# DC30_Cnet_FluxCapacitor.net
KiCad netlist of a schematic drawn in EAGLE
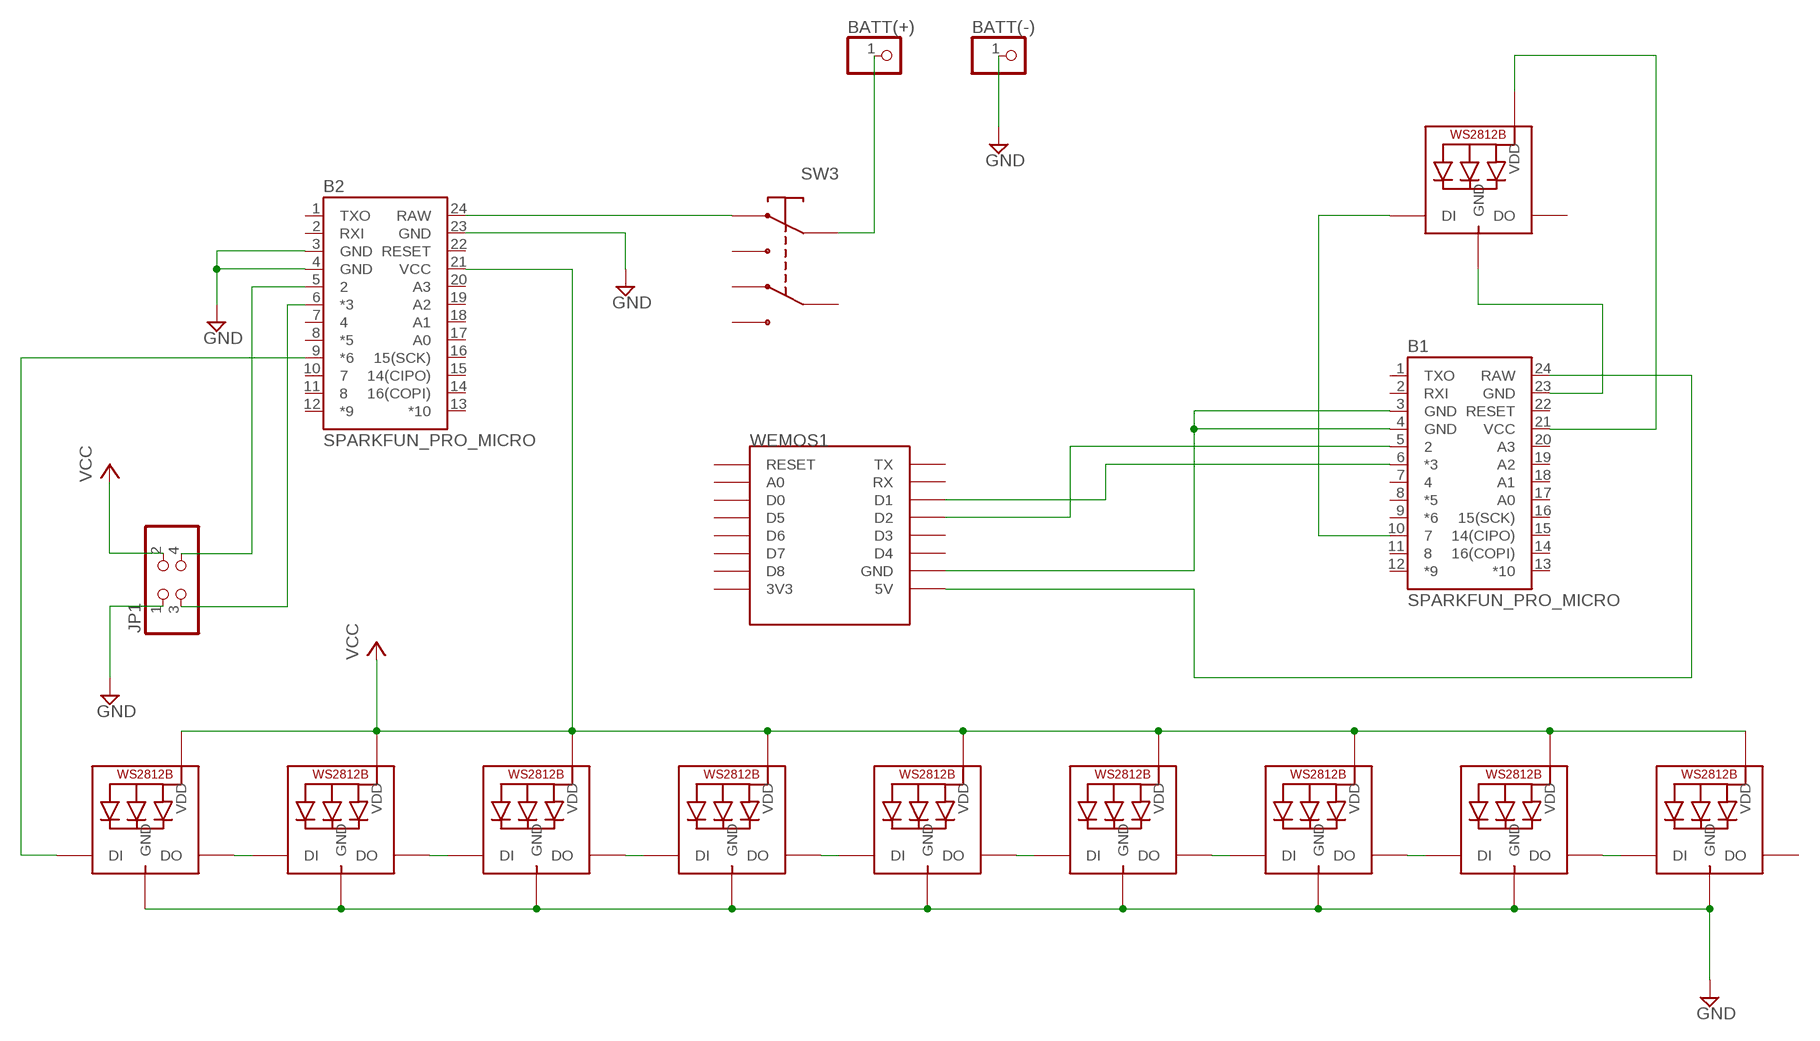
[diagram p0: schematic, sheet 1]

(export (version "E")
  (design (tool "Eeschema 10.0.6"))
  (components
    (comp (ref "B1")
      (value "SPARKFUN_PRO_MICRO")
      (footprint "eagle-import:SPARKFUN_PRO_MICRO")
      (libsource (lib "eagle-import") (part "SPARKFUN_PRO_MICRO"))
    )
    (comp (ref "B2")
      (value "SPARKFUN_PRO_MICRO")
      (footprint "eagle-import:SPARKFUN_PRO_MICRO")
      (libsource (lib "eagle-import") (part "SPARKFUN_PRO_MICRO"))
    )
    (comp (ref "BATT(+)")
      (value "PINHD-1X1")
      (footprint "eagle-import:1X01")
      (libsource (lib "eagle-import") (part "PINHD-1X1"))
    )
    (comp (ref "BATT(-)")
      (value "PINHD-1X1")
      (footprint "eagle-import:1X01")
      (libsource (lib "eagle-import") (part "PINHD-1X1"))
    )
    (comp (ref "JP1")
      (value "PINHD-2X2")
      (footprint "eagle-import:2X02")
      (libsource (lib "eagle-import") (part "PINHD-2X2"))
    )
    (comp (ref "LED1")
      (value "WS2812B5050")
      (footprint "eagle-import:WS2812B")
      (libsource (lib "eagle-import") (part "WS2812B5050"))
    )
    (comp (ref "LED2")
      (value "WS2812B5050")
      (footprint "eagle-import:WS2812B")
      (libsource (lib "eagle-import") (part "WS2812B5050"))
    )
    (comp (ref "LED3")
      (value "WS2812B5050")
      (footprint "eagle-import:WS2812B")
      (libsource (lib "eagle-import") (part "WS2812B5050"))
    )
    (comp (ref "LED4")
      (value "WS2812B5050")
      (footprint "eagle-import:WS2812B")
      (libsource (lib "eagle-import") (part "WS2812B5050"))
    )
    (comp (ref "LED5")
      (value "WS2812B5050")
      (footprint "eagle-import:WS2812B")
      (libsource (lib "eagle-import") (part "WS2812B5050"))
    )
    (comp (ref "LED6")
      (value "WS2812B5050")
      (footprint "eagle-import:WS2812B")
      (libsource (lib "eagle-import") (part "WS2812B5050"))
    )
    (comp (ref "LED7")
      (value "WS2812B5050")
      (footprint "eagle-import:WS2812B")
      (libsource (lib "eagle-import") (part "WS2812B5050"))
    )
    (comp (ref "LED8")
      (value "WS2812B5050")
      (footprint "eagle-import:WS2812B")
      (libsource (lib "eagle-import") (part "WS2812B5050"))
    )
    (comp (ref "LED9")
      (value "WS2812B5050")
      (footprint "eagle-import:WS2812B")
      (libsource (lib "eagle-import") (part "WS2812B5050"))
    )
    (comp (ref "LED10")
      (value "WS2812B5050")
      (footprint "eagle-import:WS2812B")
      (libsource (lib "eagle-import") (part "WS2812B5050"))
    )
    (comp (ref "SW3")
      (value "JS202011AQN")
      (footprint "eagle-import:JS202011AQN")
      (libsource (lib "eagle-import") (part "JS202011AQN"))
    )
    (comp (ref "WEMOS1")
      (value "WEMOS-D1-MINI")
      (footprint "eagle-import:WEMOS-D1-MINI")
      (libsource (lib "eagle-import") (part "WEMOS-D1-MINI"))
    )
  )
  (nets
    (net (code "1") (name "GND") (class "Default")
      (node (ref "B2") (pin "23") (pinfunction "GND_23") (pintype "power_in"))
      (node (ref "B2") (pin "3") (pinfunction "GND_3") (pintype "power_in"))
      (node (ref "B2") (pin "4") (pinfunction "GND_4") (pintype "power_in"))
      (node (ref "BATT(-)") (pin "1") (pinfunction "1_1") (pintype "passive"))
      (node (ref "JP1") (pin "1") (pinfunction "1_1") (pintype "passive"))
      (node (ref "LED1") (pin "3-GND") (pinfunction "GND_3-GND") (pintype "power_in"))
      (node (ref "LED2") (pin "3-GND") (pinfunction "GND_3-GND") (pintype "power_in"))
      (node (ref "LED3") (pin "3-GND") (pinfunction "GND_3-GND") (pintype "power_in"))
      (node (ref "LED4") (pin "3-GND") (pinfunction "GND_3-GND") (pintype "power_in"))
      (node (ref "LED5") (pin "3-GND") (pinfunction "GND_3-GND") (pintype "power_in"))
      (node (ref "LED6") (pin "3-GND") (pinfunction "GND_3-GND") (pintype "power_in"))
      (node (ref "LED7") (pin "3-GND") (pinfunction "GND_3-GND") (pintype "power_in"))
      (node (ref "LED8") (pin "3-GND") (pinfunction "GND_3-GND") (pintype "power_in"))
      (node (ref "LED9") (pin "3-GND") (pinfunction "GND_3-GND") (pintype "power_in"))
    )
    (net (code "2") (name "Net-(B1-*3)") (class "Default")
      (node (ref "B1") (pin "6") (pinfunction "*3_6") (pintype "bidirectional"))
      (node (ref "WEMOS1") (pin "D1") (pinfunction "D1_D1") (pintype "bidirectional"))
    )
    (net (code "3") (name "Net-(B1-2)") (class "Default")
      (node (ref "B1") (pin "5") (pinfunction "2_5") (pintype "bidirectional"))
      (node (ref "WEMOS1") (pin "D2") (pinfunction "D2_D2") (pintype "bidirectional"))
    )
    (net (code "4") (name "Net-(B1-7)") (class "Default")
      (node (ref "B1") (pin "10") (pinfunction "7_10") (pintype "bidirectional"))
      (node (ref "LED10") (pin "4-DIN") (pinfunction "DI_4-DIN") (pintype "input"))
    )
    (net (code "5") (name "Net-(B1-GND-Pad3)") (class "Default")
      (node (ref "B1") (pin "3") (pinfunction "GND_3") (pintype "power_in"))
      (node (ref "B1") (pin "4") (pinfunction "GND_4") (pintype "power_in"))
      (node (ref "WEMOS1") (pin "GND") (pinfunction "GND_GND") (pintype "bidirectional"))
    )
    (net (code "6") (name "Net-(B1-RAW)") (class "Default")
      (node (ref "B1") (pin "24") (pinfunction "RAW_24") (pintype "power_in"))
      (node (ref "WEMOS1") (pin "5V") (pinfunction "5V_5V") (pintype "bidirectional"))
    )
    (net (code "7") (name "Net-(B1-VCC)") (class "Default")
      (node (ref "B1") (pin "21") (pinfunction "VCC_21") (pintype "power_in"))
      (node (ref "LED10") (pin "1-VDD") (pinfunction "VDD_1-VDD") (pintype "power_in"))
    )
    (net (code "8") (name "Net-(B2-*3)") (class "Default")
      (node (ref "B2") (pin "6") (pinfunction "*3_6") (pintype "bidirectional"))
      (node (ref "JP1") (pin "3") (pinfunction "3_3") (pintype "passive"))
    )
    (net (code "9") (name "Net-(B2-*6)") (class "Default")
      (node (ref "B2") (pin "9") (pinfunction "*6_9") (pintype "bidirectional"))
      (node (ref "LED1") (pin "4-DIN") (pinfunction "DI_4-DIN") (pintype "input"))
    )
    (net (code "10") (name "Net-(B2-2)") (class "Default")
      (node (ref "B2") (pin "5") (pinfunction "2_5") (pintype "bidirectional"))
      (node (ref "JP1") (pin "4") (pinfunction "4_4") (pintype "passive"))
    )
    (net (code "11") (name "Net-(B2-RAW)") (class "Default")
      (node (ref "B2") (pin "24") (pinfunction "RAW_24") (pintype "power_in"))
      (node (ref "SW3") (pin "P$1") (pinfunction "1_P$1") (pintype "bidirectional"))
    )
    (net (code "12") (name "Net-(LED1-DO)") (class "Default")
      (node (ref "LED1") (pin "2-DOUT") (pinfunction "DO_2-DOUT") (pintype "output"))
      (node (ref "LED2") (pin "4-DIN") (pinfunction "DI_4-DIN") (pintype "input"))
    )
    (net (code "13") (name "Net-(LED2-DO)") (class "Default")
      (node (ref "LED2") (pin "2-DOUT") (pinfunction "DO_2-DOUT") (pintype "output"))
      (node (ref "LED3") (pin "4-DIN") (pinfunction "DI_4-DIN") (pintype "input"))
    )
    (net (code "14") (name "Net-(LED3-DO)") (class "Default")
      (node (ref "LED3") (pin "2-DOUT") (pinfunction "DO_2-DOUT") (pintype "output"))
      (node (ref "LED4") (pin "4-DIN") (pinfunction "DI_4-DIN") (pintype "input"))
    )
    (net (code "15") (name "Net-(LED4-DO)") (class "Default")
      (node (ref "LED4") (pin "2-DOUT") (pinfunction "DO_2-DOUT") (pintype "output"))
      (node (ref "LED5") (pin "4-DIN") (pinfunction "DI_4-DIN") (pintype "input"))
    )
    (net (code "16") (name "Net-(LED5-DO)") (class "Default")
      (node (ref "LED5") (pin "2-DOUT") (pinfunction "DO_2-DOUT") (pintype "output"))
      (node (ref "LED6") (pin "4-DIN") (pinfunction "DI_4-DIN") (pintype "input"))
    )
    (net (code "17") (name "Net-(LED6-DO)") (class "Default")
      (node (ref "LED6") (pin "2-DOUT") (pinfunction "DO_2-DOUT") (pintype "output"))
      (node (ref "LED7") (pin "4-DIN") (pinfunction "DI_4-DIN") (pintype "input"))
    )
    (net (code "18") (name "Net-(LED7-DO)") (class "Default")
      (node (ref "LED7") (pin "2-DOUT") (pinfunction "DO_2-DOUT") (pintype "output"))
      (node (ref "LED8") (pin "4-DIN") (pinfunction "DI_4-DIN") (pintype "input"))
    )
    (net (code "19") (name "Net-(LED8-DO)") (class "Default")
      (node (ref "LED8") (pin "2-DOUT") (pinfunction "DO_2-DOUT") (pintype "output"))
      (node (ref "LED9") (pin "4-DIN") (pinfunction "DI_4-DIN") (pintype "input"))
    )
    (net (code "20") (name "Net-(LED10-GND)") (class "Default")
      (node (ref "B1") (pin "23") (pinfunction "GND_23") (pintype "power_in"))
      (node (ref "LED10") (pin "3-GND") (pinfunction "GND_3-GND") (pintype "power_in"))
    )
    (net (code "21") (name "Net-(SW3-2)") (class "Default")
      (node (ref "BATT(+)") (pin "1") (pinfunction "1_1") (pintype "passive"))
      (node (ref "SW3") (pin "P$2") (pinfunction "2_P$2") (pintype "bidirectional"))
    )
    (net (code "22") (name "VCC") (class "Default")
      (node (ref "B2") (pin "21") (pinfunction "VCC_21") (pintype "power_in"))
      (node (ref "JP1") (pin "2") (pinfunction "2_2") (pintype "passive"))
      (node (ref "LED1") (pin "1-VDD") (pinfunction "VDD_1-VDD") (pintype "power_in"))
      (node (ref "LED2") (pin "1-VDD") (pinfunction "VDD_1-VDD") (pintype "power_in"))
      (node (ref "LED3") (pin "1-VDD") (pinfunction "VDD_1-VDD") (pintype "power_in"))
      (node (ref "LED4") (pin "1-VDD") (pinfunction "VDD_1-VDD") (pintype "power_in"))
      (node (ref "LED5") (pin "1-VDD") (pinfunction "VDD_1-VDD") (pintype "power_in"))
      (node (ref "LED6") (pin "1-VDD") (pinfunction "VDD_1-VDD") (pintype "power_in"))
      (node (ref "LED7") (pin "1-VDD") (pinfunction "VDD_1-VDD") (pintype "power_in"))
      (node (ref "LED8") (pin "1-VDD") (pinfunction "VDD_1-VDD") (pintype "power_in"))
      (node (ref "LED9") (pin "1-VDD") (pinfunction "VDD_1-VDD") (pintype "power_in"))
    )
    (net (code "23") (name "unconnected-(B1-*5-Pad8)") (class "Default")
      (node (ref "B1") (pin "8") (pinfunction "*5_8") (pintype "bidirectional"))
    )
    (net (code "24") (name "unconnected-(B1-*6-Pad9)") (class "Default")
      (node (ref "B1") (pin "9") (pinfunction "*6_9") (pintype "bidirectional"))
    )
    (net (code "25") (name "unconnected-(B1-*9-Pad12)") (class "Default")
      (node (ref "B1") (pin "12") (pinfunction "*9_12") (pintype "bidirectional"))
    )
    (net (code "26") (name "unconnected-(B1-*10-Pad13)") (class "Default")
      (node (ref "B1") (pin "13") (pinfunction "*10_13") (pintype "bidirectional"))
    )
    (net (code "27") (name "unconnected-(B1-4-Pad7)") (class "Default")
      (node (ref "B1") (pin "7") (pinfunction "4_7") (pintype "bidirectional"))
    )
    (net (code "28") (name "unconnected-(B1-8-Pad11)") (class "Default")
      (node (ref "B1") (pin "11") (pinfunction "8_11") (pintype "bidirectional"))
    )
    (net (code "29") (name "unconnected-(B1-14(CIPO)-Pad15)") (class "Default")
      (node (ref "B1") (pin "15") (pinfunction "14(CIPO)_15") (pintype "bidirectional"))
    )
    (net (code "30") (name "unconnected-(B1-15(SCK)-Pad16)") (class "Default")
      (node (ref "B1") (pin "16") (pinfunction "15(SCK)_16") (pintype "bidirectional"))
    )
    (net (code "31") (name "unconnected-(B1-16(COPI)-Pad14)") (class "Default")
      (node (ref "B1") (pin "14") (pinfunction "16(COPI)_14") (pintype "bidirectional"))
    )
    (net (code "32") (name "unconnected-(B1-A0-Pad17)") (class "Default")
      (node (ref "B1") (pin "17") (pinfunction "A0_17") (pintype "bidirectional"))
    )
    (net (code "33") (name "unconnected-(B1-A1-Pad18)") (class "Default")
      (node (ref "B1") (pin "18") (pinfunction "A1_18") (pintype "bidirectional"))
    )
    (net (code "34") (name "unconnected-(B1-A2-Pad19)") (class "Default")
      (node (ref "B1") (pin "19") (pinfunction "A2_19") (pintype "bidirectional"))
    )
    (net (code "35") (name "unconnected-(B1-A3-Pad20)") (class "Default")
      (node (ref "B1") (pin "20") (pinfunction "A3_20") (pintype "bidirectional"))
    )
    (net (code "36") (name "unconnected-(B1-RESET-Pad22)") (class "Default")
      (node (ref "B1") (pin "22") (pinfunction "RESET_22") (pintype "bidirectional"))
    )
    (net (code "37") (name "unconnected-(B1-RXI-Pad2)") (class "Default")
      (node (ref "B1") (pin "2") (pinfunction "RXI_2") (pintype "bidirectional"))
    )
    (net (code "38") (name "unconnected-(B1-TXO-Pad1)") (class "Default")
      (node (ref "B1") (pin "1") (pinfunction "TXO_1") (pintype "bidirectional"))
    )
    (net (code "39") (name "unconnected-(B2-*5-Pad8)") (class "Default")
      (node (ref "B2") (pin "8") (pinfunction "*5_8") (pintype "bidirectional"))
    )
    (net (code "40") (name "unconnected-(B2-*9-Pad12)") (class "Default")
      (node (ref "B2") (pin "12") (pinfunction "*9_12") (pintype "bidirectional"))
    )
    (net (code "41") (name "unconnected-(B2-*10-Pad13)") (class "Default")
      (node (ref "B2") (pin "13") (pinfunction "*10_13") (pintype "bidirectional"))
    )
    (net (code "42") (name "unconnected-(B2-4-Pad7)") (class "Default")
      (node (ref "B2") (pin "7") (pinfunction "4_7") (pintype "bidirectional"))
    )
    (net (code "43") (name "unconnected-(B2-7-Pad10)") (class "Default")
      (node (ref "B2") (pin "10") (pinfunction "7_10") (pintype "bidirectional"))
    )
    (net (code "44") (name "unconnected-(B2-8-Pad11)") (class "Default")
      (node (ref "B2") (pin "11") (pinfunction "8_11") (pintype "bidirectional"))
    )
    (net (code "45") (name "unconnected-(B2-14(CIPO)-Pad15)") (class "Default")
      (node (ref "B2") (pin "15") (pinfunction "14(CIPO)_15") (pintype "bidirectional"))
    )
    (net (code "46") (name "unconnected-(B2-15(SCK)-Pad16)") (class "Default")
      (node (ref "B2") (pin "16") (pinfunction "15(SCK)_16") (pintype "bidirectional"))
    )
    (net (code "47") (name "unconnected-(B2-16(COPI)-Pad14)") (class "Default")
      (node (ref "B2") (pin "14") (pinfunction "16(COPI)_14") (pintype "bidirectional"))
    )
    (net (code "48") (name "unconnected-(B2-A0-Pad17)") (class "Default")
      (node (ref "B2") (pin "17") (pinfunction "A0_17") (pintype "bidirectional"))
    )
    (net (code "49") (name "unconnected-(B2-A1-Pad18)") (class "Default")
      (node (ref "B2") (pin "18") (pinfunction "A1_18") (pintype "bidirectional"))
    )
    (net (code "50") (name "unconnected-(B2-A2-Pad19)") (class "Default")
      (node (ref "B2") (pin "19") (pinfunction "A2_19") (pintype "bidirectional"))
    )
    (net (code "51") (name "unconnected-(B2-A3-Pad20)") (class "Default")
      (node (ref "B2") (pin "20") (pinfunction "A3_20") (pintype "bidirectional"))
    )
    (net (code "52") (name "unconnected-(B2-RESET-Pad22)") (class "Default")
      (node (ref "B2") (pin "22") (pinfunction "RESET_22") (pintype "bidirectional"))
    )
    (net (code "53") (name "unconnected-(B2-RXI-Pad2)") (class "Default")
      (node (ref "B2") (pin "2") (pinfunction "RXI_2") (pintype "bidirectional"))
    )
    (net (code "54") (name "unconnected-(B2-TXO-Pad1)") (class "Default")
      (node (ref "B2") (pin "1") (pinfunction "TXO_1") (pintype "bidirectional"))
    )
    (net (code "55") (name "unconnected-(LED9-DO-Pad2-DOUT)") (class "Default")
      (node (ref "LED9") (pin "2-DOUT") (pinfunction "DO_2-DOUT") (pintype "output"))
    )
    (net (code "56") (name "unconnected-(LED10-DO-Pad2-DOUT)") (class "Default")
      (node (ref "LED10") (pin "2-DOUT") (pinfunction "DO_2-DOUT") (pintype "output"))
    )
    (net (code "57") (name "unconnected-(SW3-3-PadP$3)") (class "Default")
      (node (ref "SW3") (pin "P$3") (pinfunction "3_P$3") (pintype "bidirectional"))
    )
    (net (code "58") (name "unconnected-(SW3-4-PadP$4)") (class "Default")
      (node (ref "SW3") (pin "P$4") (pinfunction "4_P$4") (pintype "bidirectional"))
    )
    (net (code "59") (name "unconnected-(SW3-5-PadP$5)") (class "Default")
      (node (ref "SW3") (pin "P$5") (pinfunction "5_P$5") (pintype "bidirectional"))
    )
    (net (code "60") (name "unconnected-(SW3-6-PadP$6)") (class "Default")
      (node (ref "SW3") (pin "P$6") (pinfunction "6_P$6") (pintype "bidirectional"))
    )
    (net (code "61") (name "unconnected-(WEMOS1-Pad3V3)") (class "Default")
      (node (ref "WEMOS1") (pin "3V3") (pinfunction "3V3_3V3") (pintype "bidirectional"))
    )
    (net (code "62") (name "unconnected-(WEMOS1-PadA0)") (class "Default")
      (node (ref "WEMOS1") (pin "A0") (pinfunction "A0_A0") (pintype "bidirectional"))
    )
    (net (code "63") (name "unconnected-(WEMOS1-PadD0)") (class "Default")
      (node (ref "WEMOS1") (pin "D0") (pinfunction "D0_D0") (pintype "bidirectional"))
    )
    (net (code "64") (name "unconnected-(WEMOS1-PadD3)") (class "Default")
      (node (ref "WEMOS1") (pin "D3") (pinfunction "D3_D3") (pintype "bidirectional"))
    )
    (net (code "65") (name "unconnected-(WEMOS1-PadD4)") (class "Default")
      (node (ref "WEMOS1") (pin "D4") (pinfunction "D4_D4") (pintype "bidirectional"))
    )
    (net (code "66") (name "unconnected-(WEMOS1-PadD5)") (class "Default")
      (node (ref "WEMOS1") (pin "D5") (pinfunction "D5_D5") (pintype "bidirectional"))
    )
    (net (code "67") (name "unconnected-(WEMOS1-PadD6)") (class "Default")
      (node (ref "WEMOS1") (pin "D6") (pinfunction "D6_D6") (pintype "bidirectional"))
    )
    (net (code "68") (name "unconnected-(WEMOS1-PadD7)") (class "Default")
      (node (ref "WEMOS1") (pin "D7") (pinfunction "D7_D7") (pintype "bidirectional"))
    )
    (net (code "69") (name "unconnected-(WEMOS1-PadD8)") (class "Default")
      (node (ref "WEMOS1") (pin "D8") (pinfunction "D8_D8") (pintype "bidirectional"))
    )
    (net (code "70") (name "unconnected-(WEMOS1-PadRESET)") (class "Default")
      (node (ref "WEMOS1") (pin "RESET") (pinfunction "RESET_RESET") (pintype "bidirectional"))
    )
    (net (code "71") (name "unconnected-(WEMOS1-PadRX)") (class "Default")
      (node (ref "WEMOS1") (pin "RX") (pinfunction "RX_RX") (pintype "bidirectional"))
    )
    (net (code "72") (name "unconnected-(WEMOS1-PadTX)") (class "Default")
      (node (ref "WEMOS1") (pin "TX") (pinfunction "TX_TX") (pintype "bidirectional"))
    )
  )
)
